# Radio_Receiver.net
KiCad netlist of a schematic drawn in EAGLE
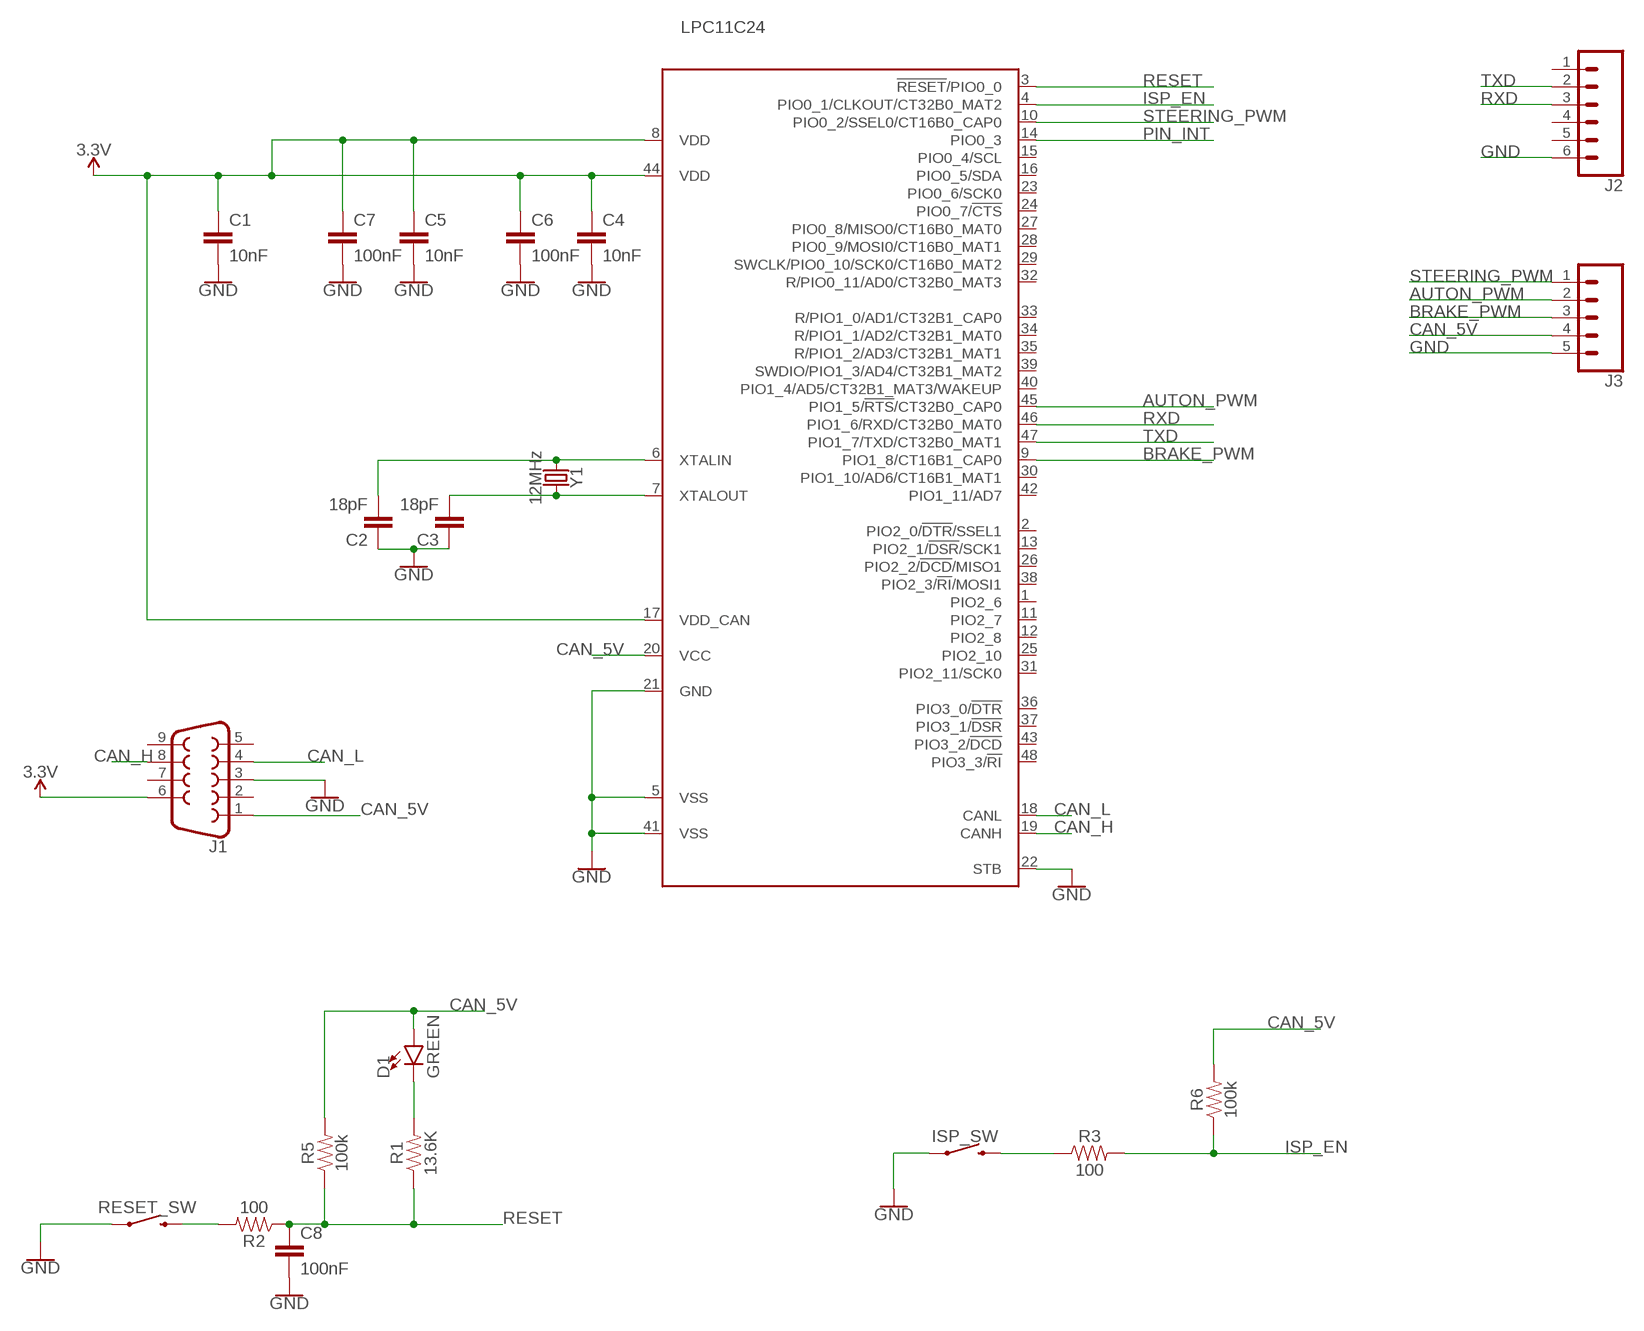
[diagram p0: schematic, sheet 1]

(export (version "E")
  (design (tool "Eeschema 10.0.6"))
  (components
    (comp (ref "C1")
      (value "10nF")
      (footprint "eagle-import:CAP-PTH-2.54")
      (libsource (lib "eagle-import") (part "22PF-PTH-2.54MM-200V-5%"))
    )
    (comp (ref "C2")
      (value "18pF")
      (footprint "eagle-import:CAP-PTH-2.54")
      (libsource (lib "eagle-import") (part "22PF-PTH-2.54MM-200V-5%"))
    )
    (comp (ref "C3")
      (value "18pF")
      (footprint "eagle-import:CAP-PTH-2.54")
      (libsource (lib "eagle-import") (part "22PF-PTH-2.54MM-200V-5%"))
    )
    (comp (ref "C4")
      (value "10nF")
      (footprint "eagle-import:CAP-PTH-2.54")
      (libsource (lib "eagle-import") (part "22PF-PTH-2.54MM-200V-5%"))
    )
    (comp (ref "C5")
      (value "10nF")
      (footprint "eagle-import:CAP-PTH-2.54")
      (libsource (lib "eagle-import") (part "22PF-PTH-2.54MM-200V-5%"))
    )
    (comp (ref "C6")
      (value "100nF")
      (footprint "eagle-import:CAP-PTH-2.54")
      (libsource (lib "eagle-import") (part "22PF-PTH-2.54MM-200V-5%"))
    )
    (comp (ref "C7")
      (value "100nF")
      (footprint "eagle-import:CAP-PTH-2.54")
      (libsource (lib "eagle-import") (part "22PF-PTH-2.54MM-200V-5%"))
    )
    (comp (ref "C8")
      (value "100nF")
      (footprint "eagle-import:CAP-PTH-2.54")
      (libsource (lib "eagle-import") (part "22PF-PTH-2.54MM-200V-5%"))
    )
    (comp (ref "D1")
      (value "GREEN")
      (footprint "eagle-import:LED-1206")
      (libsource (lib "eagle-import") (part "LED-GREEN1206"))
    )
    (comp (ref "ISP_SW")
      (value "MOMENTARY-SWITCH-SPST-PTH-6.0MM")
      (footprint "eagle-import:TACTILE_SWITCH_PTH_6.0MM")
      (libsource (lib "eagle-import") (part "MOMENTARY-SWITCH-SPST-PTH-6.0MM"))
    )
    (comp (ref "J1")
      (value "DB9FEMALE")
      (footprint "eagle-import:DB9")
      (libsource (lib "eagle-import") (part "DB9FEMALE"))
    )
    (comp (ref "J2")
      (value "CONN_06SILK_FEMALE_PTH")
      (footprint "eagle-import:1X06")
      (libsource (lib "eagle-import") (part "CONN_06SILK_FEMALE_PTH"))
    )
    (comp (ref "J3")
      (value "CONN_05")
      (footprint "eagle-import:1X05")
      (libsource (lib "eagle-import") (part "CONN_05"))
    )
    (comp (ref "LPC11C24")
      (value "LPC11C22/24-LQFP48")
      (footprint "eagle-import:LQFP48")
      (libsource (lib "eagle-import") (part "LPC11C22/24-LQFP48"))
    )
    (comp (ref "R1")
      (value "13.6K")
      (footprint "eagle-import:AXIAL-0.3")
      (libsource (lib "eagle-import") (part "100KOHM-HORIZ-1/4W-1%"))
    )
    (comp (ref "R2")
      (value "100")
      (footprint "eagle-import:AXIAL-0.3")
      (libsource (lib "eagle-import") (part "100KOHM-HORIZ-1/4W-1%"))
    )
    (comp (ref "R3")
      (value "100")
      (footprint "eagle-import:AXIAL-0.3")
      (libsource (lib "eagle-import") (part "100OHM-HORIZ-1/4W-1%"))
    )
    (comp (ref "R5")
      (value "100k")
      (footprint "eagle-import:AXIAL-0.3")
      (libsource (lib "eagle-import") (part "100KOHM-HORIZ-1/4W-1%"))
    )
    (comp (ref "R6")
      (value "100k")
      (footprint "eagle-import:AXIAL-0.3")
      (libsource (lib "eagle-import") (part "100KOHM-HORIZ-1/4W-1%"))
    )
    (comp (ref "RESET_SW")
      (value "MOMENTARY-SWITCH-SPST-PTH-6.0MM")
      (footprint "eagle-import:TACTILE_SWITCH_PTH_6.0MM")
      (libsource (lib "eagle-import") (part "MOMENTARY-SWITCH-SPST-PTH-6.0MM"))
    )
    (comp (ref "Y1")
      (value "12MHz")
      (footprint "eagle-import:HC49US")
      (libsource (lib "eagle-import") (part "CRYSTAL-16MHZPTH-HC49US"))
    )
  )
  (nets
    (net (code "1") (name "/AUTON_PWM") (class "Default")
      (node (ref "J3") (pin "2") (pinfunction "2_2") (pintype "passive"))
      (node (ref "LPC11C24") (pin "45") (pinfunction "PIO1_5/~{RTS}/CT32B0_CAP0_45") (pintype "bidirectional"))
    )
    (net (code "2") (name "/BRAKE_PWM") (class "Default")
      (node (ref "J3") (pin "3") (pinfunction "3_3") (pintype "passive"))
      (node (ref "LPC11C24") (pin "9") (pinfunction "PIO1_8/CT16B1_CAP0_9") (pintype "bidirectional"))
    )
    (net (code "3") (name "/CAN_5V") (class "Default")
      (node (ref "D1") (pin "A") (pinfunction "A_A") (pintype "passive"))
      (node (ref "J1") (pin "1") (pinfunction "1_1") (pintype "passive"))
      (node (ref "J3") (pin "4") (pinfunction "4_4") (pintype "passive"))
      (node (ref "LPC11C24") (pin "20") (pinfunction "VCC_20") (pintype "power_in"))
      (node (ref "R5") (pin "P$2") (pinfunction "2_P$2") (pintype "passive"))
      (node (ref "R6") (pin "P$2") (pinfunction "2_P$2") (pintype "passive"))
    )
    (net (code "4") (name "/CAN_H") (class "Default")
      (node (ref "J1") (pin "8") (pinfunction "8_8") (pintype "passive"))
      (node (ref "LPC11C24") (pin "19") (pinfunction "CANH_19") (pintype "bidirectional"))
    )
    (net (code "5") (name "/CAN_L") (class "Default")
      (node (ref "J1") (pin "4") (pinfunction "4_4") (pintype "passive"))
      (node (ref "LPC11C24") (pin "18") (pinfunction "CANL_18") (pintype "bidirectional"))
    )
    (net (code "6") (name "/ISP_EN") (class "Default")
      (node (ref "LPC11C24") (pin "4") (pinfunction "PIO0_1/CLKOUT/CT32B0_MAT2_4") (pintype "bidirectional"))
      (node (ref "R3") (pin "P$2") (pinfunction "2_P$2") (pintype "passive"))
      (node (ref "R6") (pin "P$1") (pinfunction "1_P$1") (pintype "passive"))
    )
    (net (code "7") (name "/PIN_INT") (class "Default")
      (node (ref "LPC11C24") (pin "14") (pinfunction "PIO0_3_14") (pintype "bidirectional"))
    )
    (net (code "8") (name "/RESET") (class "Default")
      (node (ref "C8") (pin "1") (pinfunction "1_1") (pintype "passive"))
      (node (ref "LPC11C24") (pin "3") (pinfunction "~{RESET}/PIO0_0_3") (pintype "bidirectional"))
      (node (ref "R1") (pin "P$1") (pinfunction "1_P$1") (pintype "passive"))
      (node (ref "R2") (pin "P$1") (pinfunction "1_P$1") (pintype "passive"))
      (node (ref "R5") (pin "P$1") (pinfunction "1_P$1") (pintype "passive"))
    )
    (net (code "9") (name "/RXD") (class "Default")
      (node (ref "J2") (pin "3") (pinfunction "3_3") (pintype "passive"))
      (node (ref "LPC11C24") (pin "46") (pinfunction "PIO1_6/RXD/CT32B0_MAT0_46") (pintype "bidirectional"))
    )
    (net (code "10") (name "/STEERING_PWM") (class "Default")
      (node (ref "J3") (pin "1") (pinfunction "1_1") (pintype "passive"))
      (node (ref "LPC11C24") (pin "10") (pinfunction "PIO0_2/SSEL0/CT16B0_CAP0_10") (pintype "bidirectional"))
    )
    (net (code "11") (name "/TXD") (class "Default")
      (node (ref "J2") (pin "2") (pinfunction "2_2") (pintype "passive"))
      (node (ref "LPC11C24") (pin "47") (pinfunction "PIO1_7/TXD/CT32B0_MAT1_47") (pintype "bidirectional"))
    )
    (net (code "12") (name "3.3V") (class "Default")
      (node (ref "C1") (pin "1") (pinfunction "1_1") (pintype "passive"))
      (node (ref "C4") (pin "1") (pinfunction "1_1") (pintype "passive"))
      (node (ref "C5") (pin "1") (pinfunction "1_1") (pintype "passive"))
      (node (ref "C6") (pin "1") (pinfunction "1_1") (pintype "passive"))
      (node (ref "C7") (pin "1") (pinfunction "1_1") (pintype "passive"))
      (node (ref "J1") (pin "6") (pinfunction "6_6") (pintype "passive"))
      (node (ref "LPC11C24") (pin "17") (pinfunction "VDD_CAN_17") (pintype "power_in"))
      (node (ref "LPC11C24") (pin "44") (pinfunction "VDD_44") (pintype "power_in"))
      (node (ref "LPC11C24") (pin "8") (pinfunction "VDD_8") (pintype "power_in"))
    )
    (net (code "13") (name "GND") (class "Default")
      (node (ref "C1") (pin "2") (pinfunction "2_2") (pintype "passive"))
      (node (ref "C2") (pin "1") (pinfunction "1_1") (pintype "passive"))
      (node (ref "C3") (pin "1") (pinfunction "1_1") (pintype "passive"))
      (node (ref "C4") (pin "2") (pinfunction "2_2") (pintype "passive"))
      (node (ref "C5") (pin "2") (pinfunction "2_2") (pintype "passive"))
      (node (ref "C6") (pin "2") (pinfunction "2_2") (pintype "passive"))
      (node (ref "C7") (pin "2") (pinfunction "2_2") (pintype "passive"))
      (node (ref "C8") (pin "2") (pinfunction "2_2") (pintype "passive"))
      (node (ref "ISP_SW") (pin "1") (pinfunction "1_1") (pintype "passive"))
      (node (ref "J1") (pin "3") (pinfunction "3_3") (pintype "passive"))
      (node (ref "J2") (pin "6") (pinfunction "6_6") (pintype "passive"))
      (node (ref "J3") (pin "5") (pinfunction "5_5") (pintype "passive"))
      (node (ref "LPC11C24") (pin "21") (pinfunction "GND_21") (pintype "power_in"))
      (node (ref "LPC11C24") (pin "22") (pinfunction "STB_22") (pintype "bidirectional"))
      (node (ref "LPC11C24") (pin "41") (pinfunction "VSS_41") (pintype "power_in"))
      (node (ref "LPC11C24") (pin "5") (pinfunction "VSS_5") (pintype "power_in"))
      (node (ref "RESET_SW") (pin "1") (pinfunction "1_1") (pintype "passive"))
    )
    (net (code "14") (name "Net-(ISP_SW-2)") (class "Default")
      (node (ref "ISP_SW") (pin "3") (pinfunction "2_3") (pintype "passive"))
      (node (ref "R3") (pin "P$1") (pinfunction "1_P$1") (pintype "passive"))
    )
    (net (code "15") (name "Net-(LPC11C24-XTALIN)") (class "Default")
      (node (ref "C2") (pin "2") (pinfunction "2_2") (pintype "passive"))
      (node (ref "LPC11C24") (pin "6") (pinfunction "XTALIN_6") (pintype "passive"))
      (node (ref "Y1") (pin "1") (pinfunction "1_1") (pintype "passive"))
    )
    (net (code "16") (name "Net-(LPC11C24-XTALOUT)") (class "Default")
      (node (ref "C3") (pin "2") (pinfunction "2_2") (pintype "passive"))
      (node (ref "LPC11C24") (pin "7") (pinfunction "XTALOUT_7") (pintype "passive"))
      (node (ref "Y1") (pin "2") (pinfunction "2_2") (pintype "passive"))
    )
    (net (code "17") (name "Net-(R1-2)") (class "Default")
      (node (ref "D1") (pin "C") (pinfunction "C_C") (pintype "passive"))
      (node (ref "R1") (pin "P$2") (pinfunction "2_P$2") (pintype "passive"))
    )
    (net (code "18") (name "Net-(R2-2)") (class "Default")
      (node (ref "R2") (pin "P$2") (pinfunction "2_P$2") (pintype "passive"))
      (node (ref "RESET_SW") (pin "3") (pinfunction "2_3") (pintype "passive"))
    )
    (net (code "19") (name "unconnected-(J1-Pad2)") (class "Default")
      (node (ref "J1") (pin "2") (pinfunction "2_2") (pintype "passive"))
    )
    (net (code "20") (name "unconnected-(J1-Pad5)") (class "Default")
      (node (ref "J1") (pin "5") (pinfunction "5_5") (pintype "passive"))
    )
    (net (code "21") (name "unconnected-(J1-Pad7)") (class "Default")
      (node (ref "J1") (pin "7") (pinfunction "7_7") (pintype "passive"))
    )
    (net (code "22") (name "unconnected-(J1-Pad9)") (class "Default")
      (node (ref "J1") (pin "9") (pinfunction "9_9") (pintype "passive"))
    )
    (net (code "23") (name "unconnected-(J2-Pad1)") (class "Default")
      (node (ref "J2") (pin "1") (pinfunction "1_1") (pintype "passive"))
    )
    (net (code "24") (name "unconnected-(J2-Pad4)") (class "Default")
      (node (ref "J2") (pin "4") (pinfunction "4_4") (pintype "passive"))
    )
    (net (code "25") (name "unconnected-(J2-Pad5)") (class "Default")
      (node (ref "J2") (pin "5") (pinfunction "5_5") (pintype "passive"))
    )
    (net (code "26") (name "unconnected-(LPC11C24-PIO0_4{slash}SCL-Pad15)") (class "Default")
      (node (ref "LPC11C24") (pin "15") (pinfunction "PIO0_4/SCL_15") (pintype "bidirectional"))
    )
    (net (code "27") (name "unconnected-(LPC11C24-PIO0_5{slash}SDA-Pad16)") (class "Default")
      (node (ref "LPC11C24") (pin "16") (pinfunction "PIO0_5/SDA_16") (pintype "bidirectional"))
    )
    (net (code "28") (name "unconnected-(LPC11C24-PIO0_6{slash}SCK0-Pad23)") (class "Default")
      (node (ref "LPC11C24") (pin "23") (pinfunction "PIO0_6/SCK0_23") (pintype "bidirectional"))
    )
    (net (code "29") (name "unconnected-(LPC11C24-PIO0_7{slash}~{CTS}-Pad24)") (class "Default")
      (node (ref "LPC11C24") (pin "24") (pinfunction "PIO0_7/~{CTS}_24") (pintype "bidirectional"))
    )
    (net (code "30") (name "unconnected-(LPC11C24-PIO0_8{slash}MISO0{slash}CT16B0_MAT0-Pad27)") (class "Default")
      (node (ref "LPC11C24") (pin "27") (pinfunction "PIO0_8/MISO0/CT16B0_MAT0_27") (pintype "bidirectional"))
    )
    (net (code "31") (name "unconnected-(LPC11C24-PIO0_9{slash}MOSI0{slash}CT16B0_MAT1-Pad28)") (class "Default")
      (node (ref "LPC11C24") (pin "28") (pinfunction "PIO0_9/MOSI0/CT16B0_MAT1_28") (pintype "bidirectional"))
    )
    (net (code "32") (name "unconnected-(LPC11C24-PIO1_4{slash}AD5{slash}CT32B1_MAT3{slash}WAKEUP-Pad40)") (class "Default")
      (node (ref "LPC11C24") (pin "40") (pinfunction "PIO1_4/AD5/CT32B1_MAT3/WAKEUP_40") (pintype "bidirectional"))
    )
    (net (code "33") (name "unconnected-(LPC11C24-PIO1_10{slash}AD6{slash}CT16B1_MAT1-Pad30)") (class "Default")
      (node (ref "LPC11C24") (pin "30") (pinfunction "PIO1_10/AD6/CT16B1_MAT1_30") (pintype "bidirectional"))
    )
    (net (code "34") (name "unconnected-(LPC11C24-PIO1_11{slash}AD7-Pad42)") (class "Default")
      (node (ref "LPC11C24") (pin "42") (pinfunction "PIO1_11/AD7_42") (pintype "bidirectional"))
    )
    (net (code "35") (name "unconnected-(LPC11C24-PIO2_0{slash}~{DTR}{slash}SSEL1-Pad2)") (class "Default")
      (node (ref "LPC11C24") (pin "2") (pinfunction "PIO2_0/~{DTR}/SSEL1_2") (pintype "bidirectional"))
    )
    (net (code "36") (name "unconnected-(LPC11C24-PIO2_1{slash}~{DSR}{slash}SCK1-Pad13)") (class "Default")
      (node (ref "LPC11C24") (pin "13") (pinfunction "PIO2_1/~{DSR}/SCK1_13") (pintype "bidirectional"))
    )
    (net (code "37") (name "unconnected-(LPC11C24-PIO2_2{slash}~{DCD}{slash}MISO1-Pad26)") (class "Default")
      (node (ref "LPC11C24") (pin "26") (pinfunction "PIO2_2/~{DCD}/MISO1_26") (pintype "bidirectional"))
    )
    (net (code "38") (name "unconnected-(LPC11C24-PIO2_3{slash}~{RI}{slash}MOSI1-Pad38)") (class "Default")
      (node (ref "LPC11C24") (pin "38") (pinfunction "PIO2_3/~{RI}/MOSI1_38") (pintype "bidirectional"))
    )
    (net (code "39") (name "unconnected-(LPC11C24-PIO2_6-Pad1)") (class "Default")
      (node (ref "LPC11C24") (pin "1") (pinfunction "PIO2_6_1") (pintype "bidirectional"))
    )
    (net (code "40") (name "unconnected-(LPC11C24-PIO2_7-Pad11)") (class "Default")
      (node (ref "LPC11C24") (pin "11") (pinfunction "PIO2_7_11") (pintype "bidirectional"))
    )
    (net (code "41") (name "unconnected-(LPC11C24-PIO2_8-Pad12)") (class "Default")
      (node (ref "LPC11C24") (pin "12") (pinfunction "PIO2_8_12") (pintype "bidirectional"))
    )
    (net (code "42") (name "unconnected-(LPC11C24-PIO2_10-Pad25)") (class "Default")
      (node (ref "LPC11C24") (pin "25") (pinfunction "PIO2_10_25") (pintype "bidirectional"))
    )
    (net (code "43") (name "unconnected-(LPC11C24-PIO2_11{slash}SCK0-Pad31)") (class "Default")
      (node (ref "LPC11C24") (pin "31") (pinfunction "PIO2_11/SCK0_31") (pintype "bidirectional"))
    )
    (net (code "44") (name "unconnected-(LPC11C24-PIO3_0{slash}~{DTR}-Pad36)") (class "Default")
      (node (ref "LPC11C24") (pin "36") (pinfunction "PIO3_0/~{DTR}_36") (pintype "bidirectional"))
    )
    (net (code "45") (name "unconnected-(LPC11C24-PIO3_1{slash}~{DSR}-Pad37)") (class "Default")
      (node (ref "LPC11C24") (pin "37") (pinfunction "PIO3_1/~{DSR}_37") (pintype "bidirectional"))
    )
    (net (code "46") (name "unconnected-(LPC11C24-PIO3_2{slash}~{DCD}-Pad43)") (class "Default")
      (node (ref "LPC11C24") (pin "43") (pinfunction "PIO3_2/~{DCD}_43") (pintype "bidirectional"))
    )
    (net (code "47") (name "unconnected-(LPC11C24-PIO3_3{slash}~{RI}-Pad48)") (class "Default")
      (node (ref "LPC11C24") (pin "48") (pinfunction "PIO3_3/~{RI}_48") (pintype "bidirectional"))
    )
    (net (code "48") (name "unconnected-(LPC11C24-R{slash}PIO0_11{slash}AD0{slash}CT32B0_MAT3-Pad32)") (class "Default")
      (node (ref "LPC11C24") (pin "32") (pinfunction "R/PIO0_11/AD0/CT32B0_MAT3_32") (pintype "bidirectional"))
    )
    (net (code "49") (name "unconnected-(LPC11C24-R{slash}PIO1_0{slash}AD1{slash}CT32B1_CAP0-Pad33)") (class "Default")
      (node (ref "LPC11C24") (pin "33") (pinfunction "R/PIO1_0/AD1/CT32B1_CAP0_33") (pintype "bidirectional"))
    )
    (net (code "50") (name "unconnected-(LPC11C24-R{slash}PIO1_1{slash}AD2{slash}CT32B1_MAT0-Pad34)") (class "Default")
      (node (ref "LPC11C24") (pin "34") (pinfunction "R/PIO1_1/AD2/CT32B1_MAT0_34") (pintype "bidirectional"))
    )
    (net (code "51") (name "unconnected-(LPC11C24-R{slash}PIO1_2{slash}AD3{slash}CT32B1_MAT1-Pad35)") (class "Default")
      (node (ref "LPC11C24") (pin "35") (pinfunction "R/PIO1_2/AD3/CT32B1_MAT1_35") (pintype "bidirectional"))
    )
    (net (code "52") (name "unconnected-(LPC11C24-SWCLK{slash}PIO0_10{slash}SCK0{slash}CT16B0_MAT2-Pad29)") (class "Default")
      (node (ref "LPC11C24") (pin "29") (pinfunction "SWCLK/PIO0_10/SCK0/CT16B0_MAT2_29") (pintype "bidirectional"))
    )
    (net (code "53") (name "unconnected-(LPC11C24-SWDIO{slash}PIO1_3{slash}AD4{slash}CT32B1_MAT2-Pad39)") (class "Default")
      (node (ref "LPC11C24") (pin "39") (pinfunction "SWDIO/PIO1_3/AD4/CT32B1_MAT2_39") (pintype "bidirectional"))
    )
  )
)
